# working.net
KiCad netlist of a schematic drawn in EAGLE
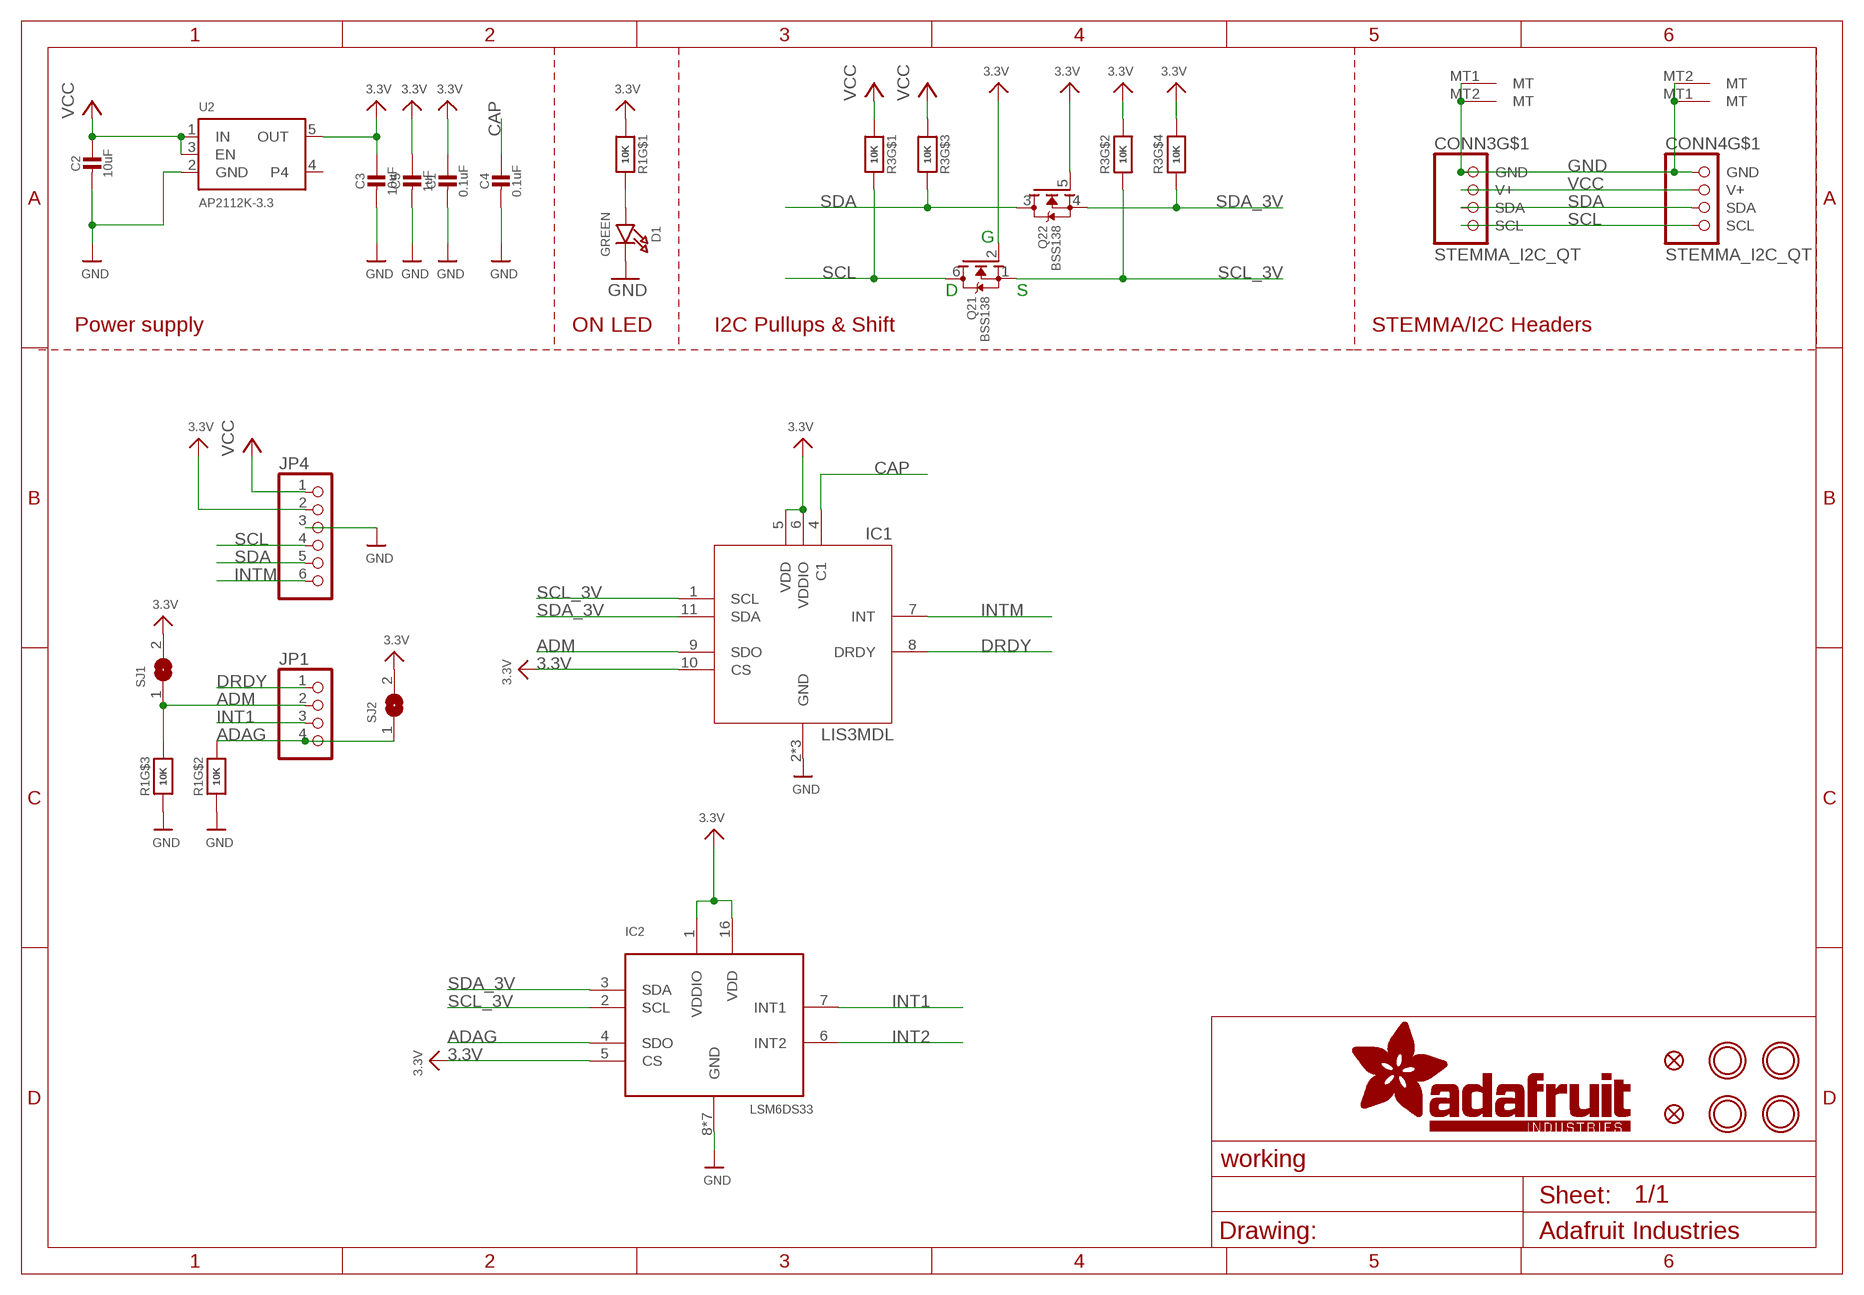
[diagram p0: schematic, sheet 1]

(export (version "E")
  (design (tool "Eeschema 10.0.6"))
  (components
    (comp (ref "C1")
      (value "0.1uF")
      (footprint "eagle-import:0603-NO")
      (libsource (lib "eagle-import") (part "CAP_CERAMIC0603_NO"))
    )
    (comp (ref "C2")
      (value "10uF")
      (footprint "eagle-import:0805-NO")
      (libsource (lib "eagle-import") (part "CAP_CERAMIC0805-NOOUTLINE"))
    )
    (comp (ref "C3")
      (value "10uF")
      (footprint "eagle-import:0805-NO")
      (libsource (lib "eagle-import") (part "CAP_CERAMIC0805-NOOUTLINE"))
    )
    (comp (ref "C4")
      (value "0.1uF")
      (footprint "eagle-import:0603-NO")
      (libsource (lib "eagle-import") (part "CAP_CERAMIC0603_NO"))
    )
    (comp (ref "C5")
      (value "1uF")
      (footprint "eagle-import:0603-NO")
      (libsource (lib "eagle-import") (part "CAP_CERAMIC0603_NO"))
    )
    (comp (ref "CONN3")
      (value "STEMMA_I2C_QT")
      (footprint "eagle-import:JST_SH4")
      (libsource (lib "eagle-import") (part "STEMMA_I2C_QT"))
    )
    (comp (ref "CONN4")
      (value "STEMMA_I2C_QT")
      (footprint "eagle-import:JST_SH4")
      (libsource (lib "eagle-import") (part "STEMMA_I2C_QT"))
    )
    (comp (ref "D1")
      (value "GREEN")
      (footprint "eagle-import:CHIPLED_0603_NOOUTLINE")
      (libsource (lib "eagle-import") (part "LED0603_NOOUTLINE"))
    )
    (comp (ref "FID3")
      (value "FIDUCIAL_1MM")
      (footprint "eagle-import:FIDUCIAL_1MM")
      (libsource (lib "eagle-import") (part "FIDUCIAL_1MM"))
    )
    (comp (ref "FID4")
      (value "FIDUCIAL_1MM")
      (footprint "eagle-import:FIDUCIAL_1MM")
      (libsource (lib "eagle-import") (part "FIDUCIAL_1MM"))
    )
    (comp (ref "IC1")
      (value "LIS3MDL")
      (footprint "eagle-import:LGA12_2X2MM")
      (libsource (lib "eagle-import") (part "LIS3MDL"))
    )
    (comp (ref "IC2")
      (value "LSM6DS33")
      (footprint "eagle-import:LGA16_3X3MM")
      (libsource (lib "eagle-import") (part "LSM6DS33"))
    )
    (comp (ref "JP1")
      (value "HEADER-1X4ROUND")
      (footprint "eagle-import:1X04_ROUND")
      (libsource (lib "eagle-import") (part "HEADER-1X4ROUND"))
    )
    (comp (ref "JP4")
      (value "HEADER-1X670MIL")
      (footprint "eagle-import:1X06_ROUND_70")
      (libsource (lib "eagle-import") (part "HEADER-1X670MIL"))
    )
    (comp (ref "Q2")
      (value "BSS138")
      (footprint "eagle-import:SOT363")
      (libsource (lib "eagle-import") (part "MOSFET-N_DUAL"))
    )
    (comp (ref "R1")
      (value "10K")
      (footprint "eagle-import:RESPACK_4X0603")
      (libsource (lib "eagle-import") (part "RESISTOR_4PACK"))
    )
    (comp (ref "R3")
      (value "10K")
      (footprint "eagle-import:RESPACK_4X0603")
      (libsource (lib "eagle-import") (part "RESISTOR_4PACK"))
    )
    (comp (ref "SJ1")
      (value "SOLDERJUMPER")
      (footprint "eagle-import:SOLDERJUMPER_ARROW_NOPASTE")
      (libsource (lib "eagle-import") (part "SOLDERJUMPER"))
    )
    (comp (ref "SJ2")
      (value "SOLDERJUMPER")
      (footprint "eagle-import:SOLDERJUMPER_ARROW_NOPASTE")
      (libsource (lib "eagle-import") (part "SOLDERJUMPER"))
    )
    (comp (ref "U$1")
      (value "MOUNTINGHOLE2.5")
      (footprint "eagle-import:MOUNTINGHOLE_2.5_PLATED")
      (libsource (lib "eagle-import") (part "MOUNTINGHOLE2.5"))
    )
    (comp (ref "U$17")
      (value "MOUNTINGHOLE2.5")
      (footprint "eagle-import:MOUNTINGHOLE_2.5_PLATED")
      (libsource (lib "eagle-import") (part "MOUNTINGHOLE2.5"))
    )
    (comp (ref "U$19")
      (value "MOUNTINGHOLE2.5")
      (footprint "eagle-import:MOUNTINGHOLE_2.5_PLATED")
      (libsource (lib "eagle-import") (part "MOUNTINGHOLE2.5"))
    )
    (comp (ref "U$21")
      (value "MOUNTINGHOLE2.5")
      (footprint "eagle-import:MOUNTINGHOLE_2.5_PLATED")
      (libsource (lib "eagle-import") (part "MOUNTINGHOLE2.5"))
    )
    (comp (ref "U2")
      (value "AP2112K-3.3")
      (footprint "eagle-import:SOT23-5")
      (libsource (lib "eagle-import") (part "VREG_SOT23-5"))
    )
  )
  (nets
    (net (code "1") (name "/ADAG") (class "Default")
      (node (ref "IC2") (pin "4") (pinfunction "SDO_4") (pintype "bidirectional"))
      (node (ref "JP1") (pin "4") (pinfunction "4_4") (pintype "passive"))
      (node (ref "R1") (pin "7") (pinfunction "2_7") (pintype "passive"))
      (node (ref "SJ2") (pin "1") (pinfunction "1_1") (pintype "passive"))
    )
    (net (code "2") (name "/ADM") (class "Default")
      (node (ref "IC1") (pin "9") (pinfunction "SDO_9") (pintype "bidirectional"))
      (node (ref "JP1") (pin "2") (pinfunction "2_2") (pintype "passive"))
      (node (ref "R1") (pin "6") (pinfunction "2_6") (pintype "passive"))
      (node (ref "SJ1") (pin "1") (pinfunction "1_1") (pintype "passive"))
    )
    (net (code "3") (name "/CAP") (class "Default")
      (node (ref "C4") (pin "1") (pinfunction "1_1") (pintype "passive"))
      (node (ref "IC1") (pin "4") (pinfunction "C1_4") (pintype "input"))
    )
    (net (code "4") (name "/DRDY") (class "Default")
      (node (ref "IC1") (pin "8") (pinfunction "DRDY_8") (pintype "output"))
      (node (ref "JP1") (pin "1") (pinfunction "1_1") (pintype "passive"))
    )
    (net (code "5") (name "/INT1") (class "Default")
      (node (ref "IC2") (pin "7") (pinfunction "INT1_7") (pintype "output"))
      (node (ref "JP1") (pin "3") (pinfunction "3_3") (pintype "passive"))
    )
    (net (code "6") (name "/INT2") (class "Default")
      (node (ref "IC2") (pin "6") (pinfunction "INT2_6") (pintype "output"))
    )
    (net (code "7") (name "/INTM") (class "Default")
      (node (ref "IC1") (pin "7") (pinfunction "INT_7") (pintype "output"))
      (node (ref "JP4") (pin "6") (pinfunction "6_6") (pintype "passive"))
    )
    (net (code "8") (name "/SCL") (class "Default")
      (node (ref "CONN3") (pin "4") (pinfunction "SCL_4") (pintype "passive"))
      (node (ref "CONN4") (pin "4") (pinfunction "SCL_4") (pintype "passive"))
      (node (ref "JP4") (pin "4") (pinfunction "4_4") (pintype "passive"))
      (node (ref "Q2") (pin "6") (pinfunction "D_6") (pintype "bidirectional"))
      (node (ref "R3") (pin "8") (pinfunction "2_8") (pintype "passive"))
    )
    (net (code "9") (name "/SCL_3V") (class "Default")
      (node (ref "IC1") (pin "1") (pinfunction "SCL_1") (pintype "input"))
      (node (ref "IC2") (pin "2") (pinfunction "SCL_2") (pintype "bidirectional"))
      (node (ref "Q2") (pin "1") (pinfunction "S_1") (pintype "bidirectional"))
      (node (ref "R3") (pin "7") (pinfunction "2_7") (pintype "passive"))
    )
    (net (code "10") (name "/SDA") (class "Default")
      (node (ref "CONN3") (pin "3") (pinfunction "SDA_3") (pintype "passive"))
      (node (ref "CONN4") (pin "3") (pinfunction "SDA_3") (pintype "passive"))
      (node (ref "JP4") (pin "5") (pinfunction "5_5") (pintype "passive"))
      (node (ref "Q2") (pin "3") (pinfunction "D_3") (pintype "bidirectional"))
      (node (ref "R3") (pin "6") (pinfunction "2_6") (pintype "passive"))
    )
    (net (code "11") (name "/SDA_3V") (class "Default")
      (node (ref "IC1") (pin "11") (pinfunction "SDA_11") (pintype "bidirectional"))
      (node (ref "IC2") (pin "3") (pinfunction "SDA_3") (pintype "bidirectional"))
      (node (ref "Q2") (pin "4") (pinfunction "S_4") (pintype "bidirectional"))
      (node (ref "R3") (pin "5") (pinfunction "2_5") (pintype "passive"))
    )
    (net (code "12") (name "3.3V") (class "Default")
      (node (ref "C1") (pin "1") (pinfunction "1_1") (pintype "passive"))
      (node (ref "C3") (pin "1") (pinfunction "1_1") (pintype "passive"))
      (node (ref "C5") (pin "1") (pinfunction "1_1") (pintype "passive"))
      (node (ref "IC1") (pin "10") (pinfunction "CS_10") (pintype "input"))
      (node (ref "IC1") (pin "5") (pinfunction "VDD_5") (pintype "power_in"))
      (node (ref "IC1") (pin "6") (pinfunction "VDDIO_6") (pintype "power_in"))
      (node (ref "IC2") (pin "1") (pinfunction "VDDIO_1") (pintype "power_in"))
      (node (ref "IC2") (pin "16") (pinfunction "VDD_16") (pintype "power_in"))
      (node (ref "IC2") (pin "5") (pinfunction "CS_5") (pintype "input"))
      (node (ref "JP4") (pin "2") (pinfunction "2_2") (pintype "passive"))
      (node (ref "Q2") (pin "2") (pinfunction "G_2") (pintype "bidirectional"))
      (node (ref "Q2") (pin "5") (pinfunction "G_5") (pintype "bidirectional"))
      (node (ref "R1") (pin "1") (pinfunction "1_1") (pintype "passive"))
      (node (ref "R3") (pin "2") (pinfunction "1_2") (pintype "passive"))
      (node (ref "R3") (pin "4") (pinfunction "1_4") (pintype "passive"))
      (node (ref "SJ1") (pin "2") (pinfunction "2_2") (pintype "passive"))
      (node (ref "SJ2") (pin "2") (pinfunction "2_2") (pintype "passive"))
      (node (ref "U2") (pin "5") (pinfunction "OUT_5") (pintype "power_in"))
    )
    (net (code "13") (name "GND") (class "Default")
      (node (ref "C1") (pin "2") (pinfunction "2_2") (pintype "passive"))
      (node (ref "C2") (pin "2") (pinfunction "2_2") (pintype "passive"))
      (node (ref "C3") (pin "2") (pinfunction "2_2") (pintype "passive"))
      (node (ref "C4") (pin "2") (pinfunction "2_2") (pintype "passive"))
      (node (ref "C5") (pin "2") (pinfunction "2_2") (pintype "passive"))
      (node (ref "CONN3") (pin "1") (pinfunction "GND_1") (pintype "passive"))
      (node (ref "CONN3") (pin "MT1") (pinfunction "MT_MT1") (pintype "bidirectional"))
      (node (ref "CONN3") (pin "MT2") (pinfunction "MT_MT2") (pintype "bidirectional"))
      (node (ref "CONN4") (pin "1") (pinfunction "GND_1") (pintype "passive"))
      (node (ref "CONN4") (pin "MT1") (pinfunction "MT_MT1") (pintype "bidirectional"))
      (node (ref "CONN4") (pin "MT2") (pinfunction "MT_MT2") (pintype "bidirectional"))
      (node (ref "D1") (pin "C") (pinfunction "C_C") (pintype "passive"))
      (node (ref "IC1") (pin "12") (pinfunction "GND_12") (pintype "power_in"))
      (node (ref "IC1") (pin "2") (pinfunction "GND_2") (pintype "power_in"))
      (node (ref "IC1") (pin "3") (pinfunction "GND_3") (pintype "power_in"))
      (node (ref "IC2") (pin "10") (pinfunction "GND_10") (pintype "power_in"))
      (node (ref "IC2") (pin "11") (pinfunction "GND_11") (pintype "power_in"))
      (node (ref "IC2") (pin "12") (pinfunction "GND_12") (pintype "power_in"))
      (node (ref "IC2") (pin "13") (pinfunction "GND_13") (pintype "power_in"))
      (node (ref "IC2") (pin "15") (pinfunction "GND_15") (pintype "power_in"))
      (node (ref "IC2") (pin "8") (pinfunction "GND_8") (pintype "power_in"))
      (node (ref "IC2") (pin "9") (pinfunction "GND_9") (pintype "power_in"))
      (node (ref "JP4") (pin "3") (pinfunction "3_3") (pintype "passive"))
      (node (ref "R1") (pin "2") (pinfunction "1_2") (pintype "passive"))
      (node (ref "R1") (pin "3") (pinfunction "1_3") (pintype "passive"))
      (node (ref "U2") (pin "2") (pinfunction "GND_2") (pintype "power_in"))
    )
    (net (code "14") (name "Net-(R1A-2)") (class "Default")
      (node (ref "D1") (pin "A") (pinfunction "A_A") (pintype "passive"))
      (node (ref "R1") (pin "8") (pinfunction "2_8") (pintype "passive"))
    )
    (net (code "15") (name "VCC") (class "Default")
      (node (ref "C2") (pin "1") (pinfunction "1_1") (pintype "passive"))
      (node (ref "CONN3") (pin "2") (pinfunction "V+_2") (pintype "passive"))
      (node (ref "CONN4") (pin "2") (pinfunction "V+_2") (pintype "passive"))
      (node (ref "JP4") (pin "1") (pinfunction "1_1") (pintype "passive"))
      (node (ref "R3") (pin "1") (pinfunction "1_1") (pintype "passive"))
      (node (ref "R3") (pin "3") (pinfunction "1_3") (pintype "passive"))
      (node (ref "U2") (pin "1") (pinfunction "IN_1") (pintype "power_in"))
      (node (ref "U2") (pin "3") (pinfunction "EN_3") (pintype "input"))
    )
    (net (code "16") (name "unconnected-(U2-P4-Pad4)") (class "Default")
      (node (ref "U2") (pin "4") (pinfunction "P4_4") (pintype "bidirectional"))
    )
  )
)
